# IMU.net
KiCad netlist of a schematic drawn in EAGLE
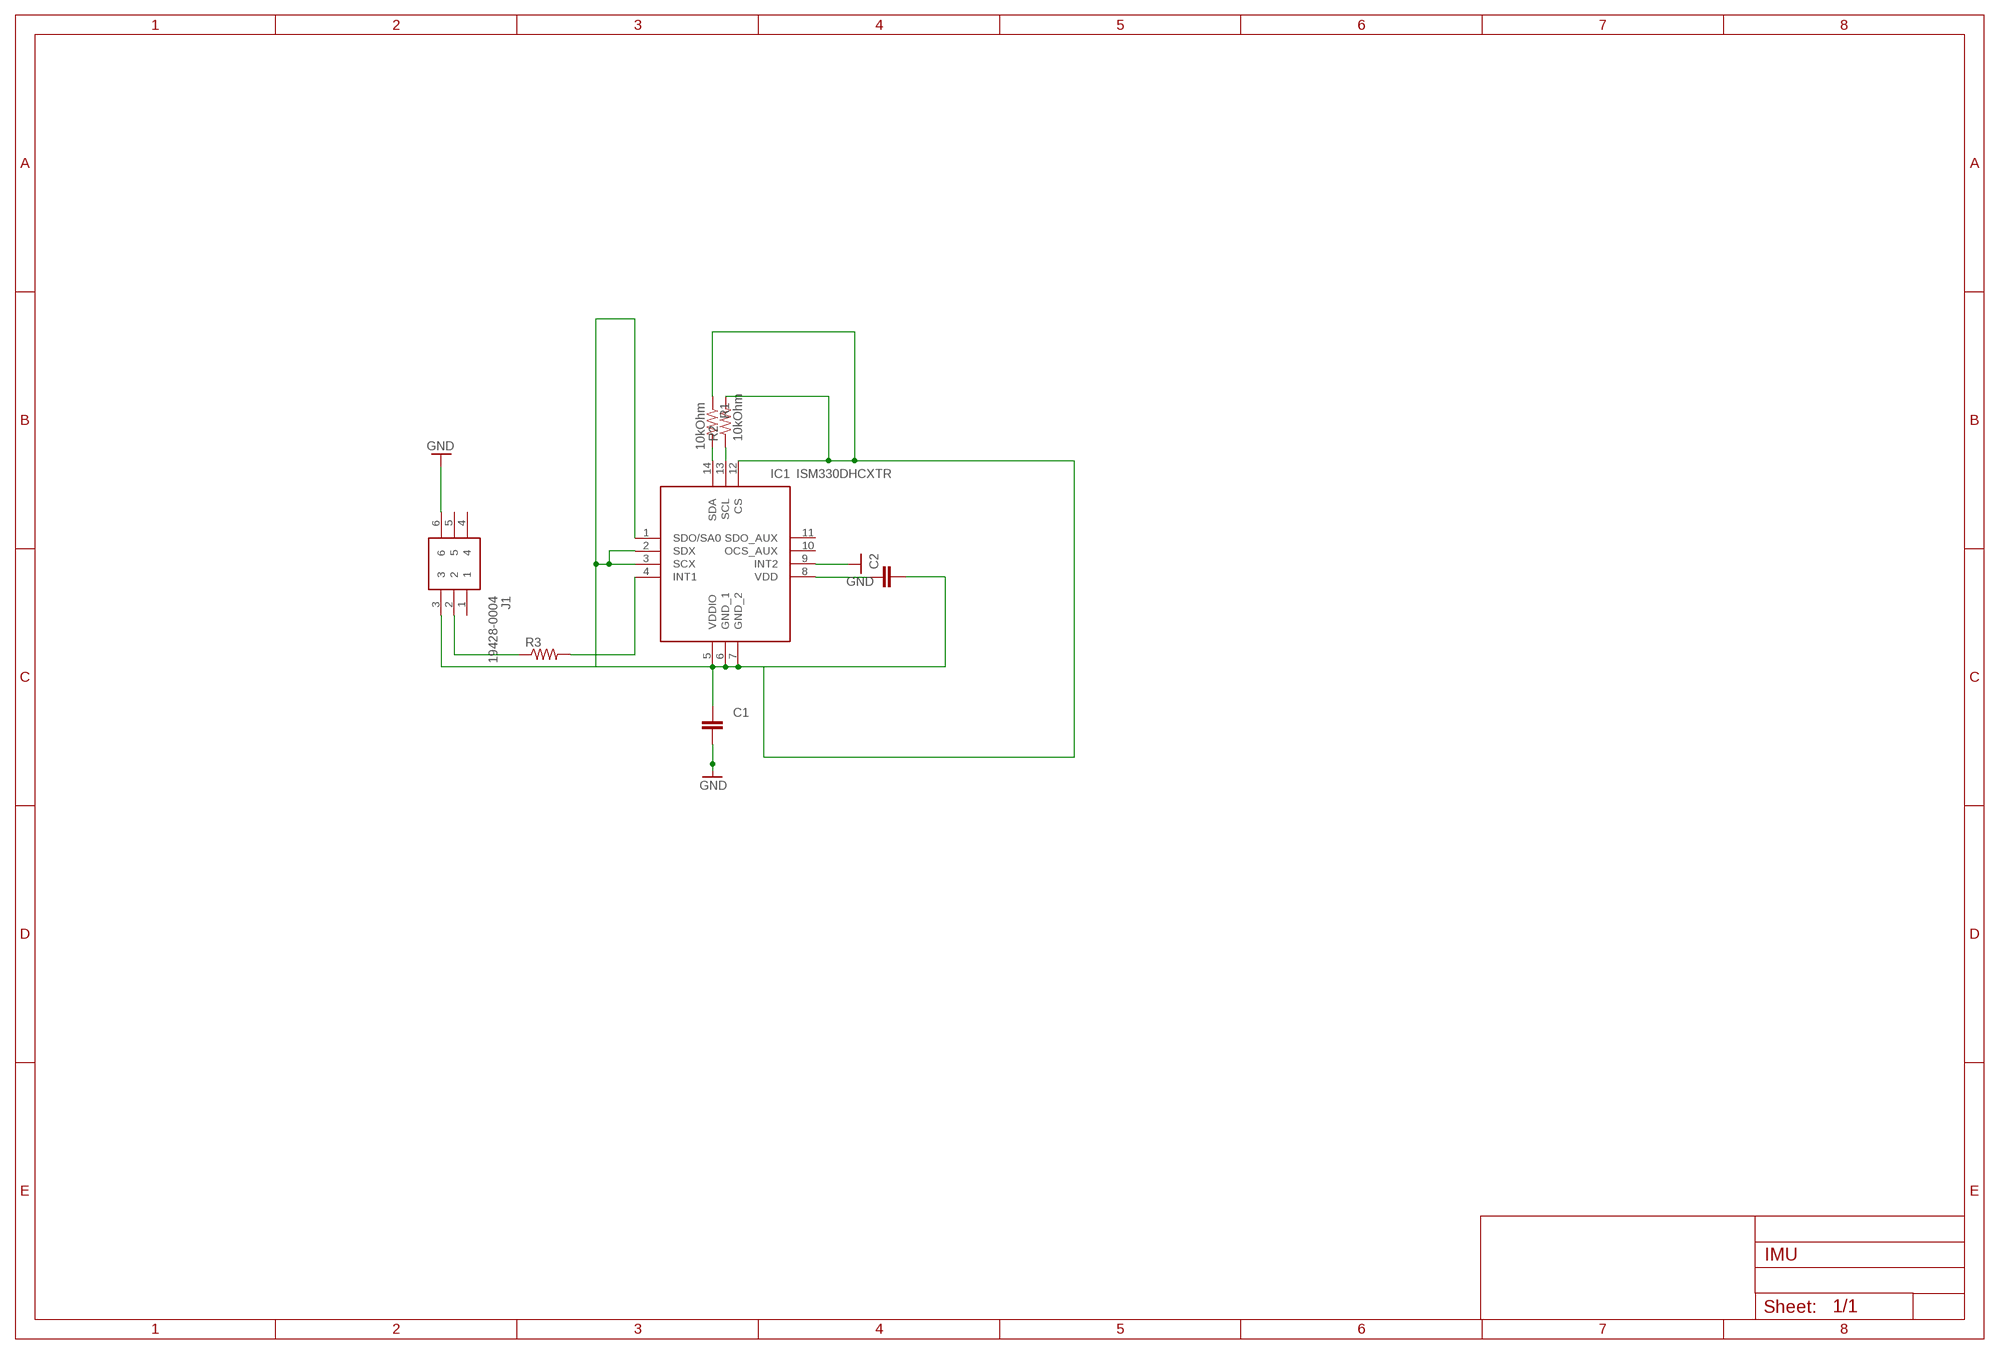
[diagram p0: schematic, sheet 1]

(export (version "E")
  (design (tool "Eeschema 10.0.6"))
  (components
    (comp (ref "C1")
      (value "C-EUC0805")
      (footprint "eagle-import:C0805")
      (libsource (lib "eagle-import") (part "C-EUC0805"))
    )
    (comp (ref "C2")
      (value "C-EUC0805")
      (footprint "eagle-import:C0805")
      (libsource (lib "eagle-import") (part "C-EUC0805"))
    )
    (comp (ref "IC1")
      (value "ISM330DHCXTR")
      (footprint "eagle-import:LGA-14(2.5X3X0.86)")
      (fields (field (name "MOUSER_PART_NUMBER") "511-ISM330DHCXTR"))
      (libsource (lib "eagle-import") (part "ISM330DHCXTR"))
    )
    (comp (ref "J1")
      (value "19428-0004")
      (footprint "eagle-import:194280004")
      (fields (field (name "MOUSER_PART_NUMBER") "538-19428-0004"))
      (libsource (lib "eagle-import") (part "19428-0004"))
    )
    (comp (ref "R1")
      (value "10kOhm")
      (footprint "eagle-import:0411_12")
      (libsource (lib "eagle-import") (part "R-US_0411/12"))
    )
    (comp (ref "R2")
      (value "10kOhm")
      (footprint "eagle-import:0411_12")
      (libsource (lib "eagle-import") (part "R-US_0411/12"))
    )
    (comp (ref "R3")
      (value "R-US_R0805")
      (footprint "eagle-import:R0805")
      (libsource (lib "eagle-import") (part "R-US_R0805"))
    )
  )
  (nets
    (net (code "1") (name "GND") (class "Default")
      (node (ref "C1") (pin "2") (pinfunction "2_2") (pintype "passive"))
      (node (ref "IC1") (pin "9") (pinfunction "INT2_9") (pintype "bidirectional"))
      (node (ref "J1") (pin "6") (pinfunction "6_6") (pintype "bidirectional"))
    )
    (net (code "2") (name "Net-(IC1-CS)") (class "Default")
      (node (ref "C1") (pin "1") (pinfunction "1_1") (pintype "passive"))
      (node (ref "C2") (pin "2") (pinfunction "2_2") (pintype "passive"))
      (node (ref "IC1") (pin "12") (pinfunction "CS_12") (pintype "bidirectional"))
      (node (ref "IC1") (pin "5") (pinfunction "VDDIO_5") (pintype "bidirectional"))
      (node (ref "IC1") (pin "6") (pinfunction "GND_1_6") (pintype "bidirectional"))
      (node (ref "IC1") (pin "7") (pinfunction "GND_2_7") (pintype "bidirectional"))
      (node (ref "J1") (pin "3") (pinfunction "3_3") (pintype "bidirectional"))
      (node (ref "R1") (pin "1") (pinfunction "1_1") (pintype "passive"))
      (node (ref "R2") (pin "2") (pinfunction "2_2") (pintype "passive"))
    )
    (net (code "3") (name "Net-(IC1-INT1)") (class "Default")
      (node (ref "IC1") (pin "4") (pinfunction "INT1_4") (pintype "bidirectional"))
      (node (ref "R3") (pin "2") (pinfunction "2_2") (pintype "passive"))
    )
    (net (code "4") (name "Net-(IC1-SCL)") (class "Default")
      (node (ref "IC1") (pin "13") (pinfunction "SCL_13") (pintype "bidirectional"))
      (node (ref "R2") (pin "1") (pinfunction "1_1") (pintype "passive"))
    )
    (net (code "5") (name "Net-(IC1-SCX)") (class "Default")
      (node (ref "IC1") (pin "1") (pinfunction "SDO/SA0_1") (pintype "bidirectional"))
      (node (ref "IC1") (pin "2") (pinfunction "SDX_2") (pintype "bidirectional"))
      (node (ref "IC1") (pin "3") (pinfunction "SCX_3") (pintype "bidirectional"))
    )
    (net (code "6") (name "Net-(IC1-SDA)") (class "Default")
      (node (ref "IC1") (pin "14") (pinfunction "SDA_14") (pintype "bidirectional"))
      (node (ref "R1") (pin "2") (pinfunction "2_2") (pintype "passive"))
    )
    (net (code "7") (name "Net-(IC1-VDD)") (class "Default")
      (node (ref "C2") (pin "1") (pinfunction "1_1") (pintype "passive"))
      (node (ref "IC1") (pin "8") (pinfunction "VDD_8") (pintype "bidirectional"))
    )
    (net (code "8") (name "Net-(J1-Pad2)") (class "Default")
      (node (ref "J1") (pin "2") (pinfunction "2_2") (pintype "bidirectional"))
      (node (ref "R3") (pin "1") (pinfunction "1_1") (pintype "passive"))
    )
    (net (code "9") (name "unconnected-(IC1-OCS_AUX-Pad10)") (class "Default")
      (node (ref "IC1") (pin "10") (pinfunction "OCS_AUX_10") (pintype "bidirectional"))
    )
    (net (code "10") (name "unconnected-(IC1-SDO_AUX-Pad11)") (class "Default")
      (node (ref "IC1") (pin "11") (pinfunction "SDO_AUX_11") (pintype "bidirectional"))
    )
    (net (code "11") (name "unconnected-(J1-Pad1)") (class "Default")
      (node (ref "J1") (pin "1") (pinfunction "1_1") (pintype "bidirectional"))
    )
    (net (code "12") (name "unconnected-(J1-Pad4)") (class "Default")
      (node (ref "J1") (pin "4") (pinfunction "4_4") (pintype "bidirectional"))
    )
    (net (code "13") (name "unconnected-(J1-Pad5)") (class "Default")
      (node (ref "J1") (pin "5") (pinfunction "5_5") (pintype "bidirectional"))
    )
  )
)
